# triangular_drawdio.net
KiCad netlist of a schematic drawn in EAGLE
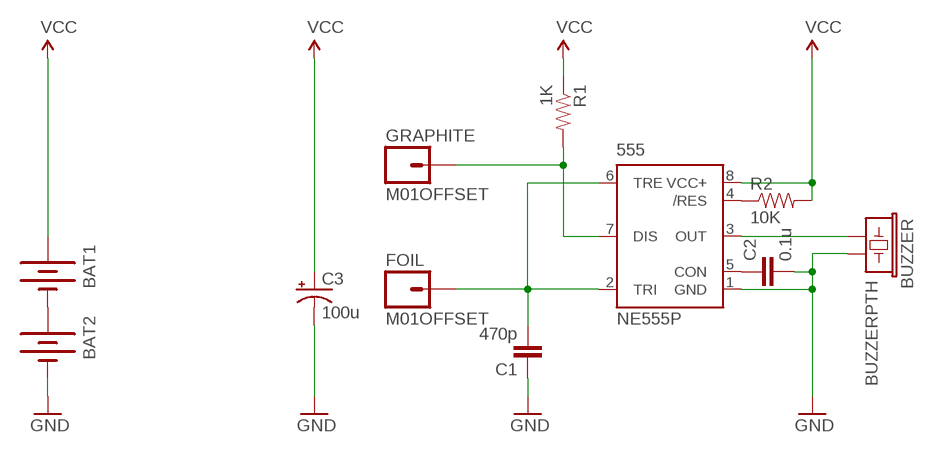
[diagram p0: schematic, sheet 1]

(export (version "E")
  (design (tool "Eeschema 10.0.6"))
  (components
    (comp (ref "555")
      (value "NE555P")
      (footprint "eagle-import:DIL-08")
      (fields (field (name "MF") "Arrow Electronics") (field (name "MPN") "NE555N"))
      (libsource (lib "eagle-import") (part "NE555P"))
    )
    (comp (ref "BAT1")
      (value "BATTERY20PTH")
      (footprint "eagle-import:BATTCOM_20MM_PTH")
      (libsource (lib "eagle-import") (part "BATTERY20PTH"))
    )
    (comp (ref "BAT2")
      (value "BATTERY20PTH")
      (footprint "eagle-import:BATTCOM_20MM_PTH")
      (libsource (lib "eagle-import") (part "BATTERY20PTH"))
    )
    (comp (ref "BUZZER")
      (value "BUZZERPTH")
      (footprint "eagle-import:BUZZER-12MM")
      (libsource (lib "eagle-import") (part "BUZZERPTH"))
    )
    (comp (ref "C1")
      (value "470p")
      (footprint "eagle-import:CAP-PTH-SMALL2")
      (libsource (lib "eagle-import") (part "CAPPTH2"))
    )
    (comp (ref "C2")
      (value "0.1u")
      (footprint "eagle-import:CAP-PTH-SMALL2")
      (libsource (lib "eagle-import") (part "CAPPTH2"))
    )
    (comp (ref "C3")
      (value "100u")
      (footprint "eagle-import:CPOL-RADIAL-10UF-25V")
      (libsource (lib "eagle-import") (part "CAP_POLPTH2"))
    )
    (comp (ref "FOIL")
      (value "M01OFFSET")
      (footprint "eagle-import:1X01_OFFSET")
      (libsource (lib "eagle-import") (part "M01OFFSET"))
    )
    (comp (ref "GRAPHITE")
      (value "M01OFFSET")
      (footprint "eagle-import:1X01_OFFSET")
      (libsource (lib "eagle-import") (part "M01OFFSET"))
    )
    (comp (ref "R1")
      (value "1K")
      (footprint "eagle-import:AXIAL-0.4")
      (libsource (lib "eagle-import") (part "RESISTORPTH-1/4W"))
    )
    (comp (ref "R2")
      (value "10K")
      (footprint "eagle-import:AXIAL-0.4")
      (libsource (lib "eagle-import") (part "RESISTORPTH-1/4W"))
    )
  )
  (nets
    (net (code "1") (name "GND") (class "Default")
      (node (ref "555") (pin "1") (pinfunction "GND_1") (pintype "power_in"))
      (node (ref "BAT2") (pin "2") (pinfunction "-_2") (pintype "power_in"))
      (node (ref "BUZZER") (pin "-") (pinfunction "2_-") (pintype "passive"))
      (node (ref "C1") (pin "1") (pinfunction "1_1") (pintype "passive"))
      (node (ref "C2") (pin "2") (pinfunction "2_2") (pintype "passive"))
      (node (ref "C3") (pin "2") (pinfunction "-_2") (pintype "passive"))
    )
    (net (code "2") (name "Net-(555-CON)") (class "Default")
      (node (ref "555") (pin "5") (pinfunction "CON_5") (pintype "input"))
      (node (ref "C2") (pin "1") (pinfunction "1_1") (pintype "passive"))
    )
    (net (code "3") (name "Net-(555-DIS)") (class "Default")
      (node (ref "555") (pin "7") (pinfunction "DIS_7") (pintype "input"))
      (node (ref "GRAPHITE") (pin "1") (pinfunction "1_1") (pintype "passive"))
      (node (ref "R1") (pin "P$2") (pinfunction "2_P$2") (pintype "passive"))
    )
    (net (code "4") (name "Net-(555-OUT)") (class "Default")
      (node (ref "555") (pin "3") (pinfunction "OUT_3") (pintype "output"))
      (node (ref "BUZZER") (pin "+") (pinfunction "1_+") (pintype "passive"))
    )
    (net (code "5") (name "Net-(555-TRE)") (class "Default")
      (node (ref "555") (pin "2") (pinfunction "TRI_2") (pintype "input"))
      (node (ref "555") (pin "6") (pinfunction "TRE_6") (pintype "input"))
      (node (ref "C1") (pin "2") (pinfunction "2_2") (pintype "passive"))
      (node (ref "FOIL") (pin "1") (pinfunction "1_1") (pintype "passive"))
    )
    (net (code "6") (name "Net-(555-{slash}RES)") (class "Default")
      (node (ref "555") (pin "4") (pinfunction "/RES_4") (pintype "input"))
      (node (ref "R2") (pin "P$1") (pinfunction "1_P$1") (pintype "passive"))
    )
    (net (code "7") (name "Net-(BAT1--)") (class "Default")
      (node (ref "BAT1") (pin "2") (pinfunction "-_2") (pintype "power_in"))
      (node (ref "BAT2") (pin "1") (pinfunction "+_1") (pintype "power_in"))
    )
    (net (code "8") (name "VCC") (class "Default")
      (node (ref "555") (pin "8") (pinfunction "VCC+_8") (pintype "power_in"))
      (node (ref "BAT1") (pin "1") (pinfunction "+_1") (pintype "power_in"))
      (node (ref "C3") (pin "1") (pinfunction "+_1") (pintype "passive"))
      (node (ref "R1") (pin "P$1") (pinfunction "1_P$1") (pintype "passive"))
      (node (ref "R2") (pin "P$2") (pinfunction "2_P$2") (pintype "passive"))
    )
  )
)
